# 8j-merge2.net
KiCad netlist of a schematic drawn in EAGLE
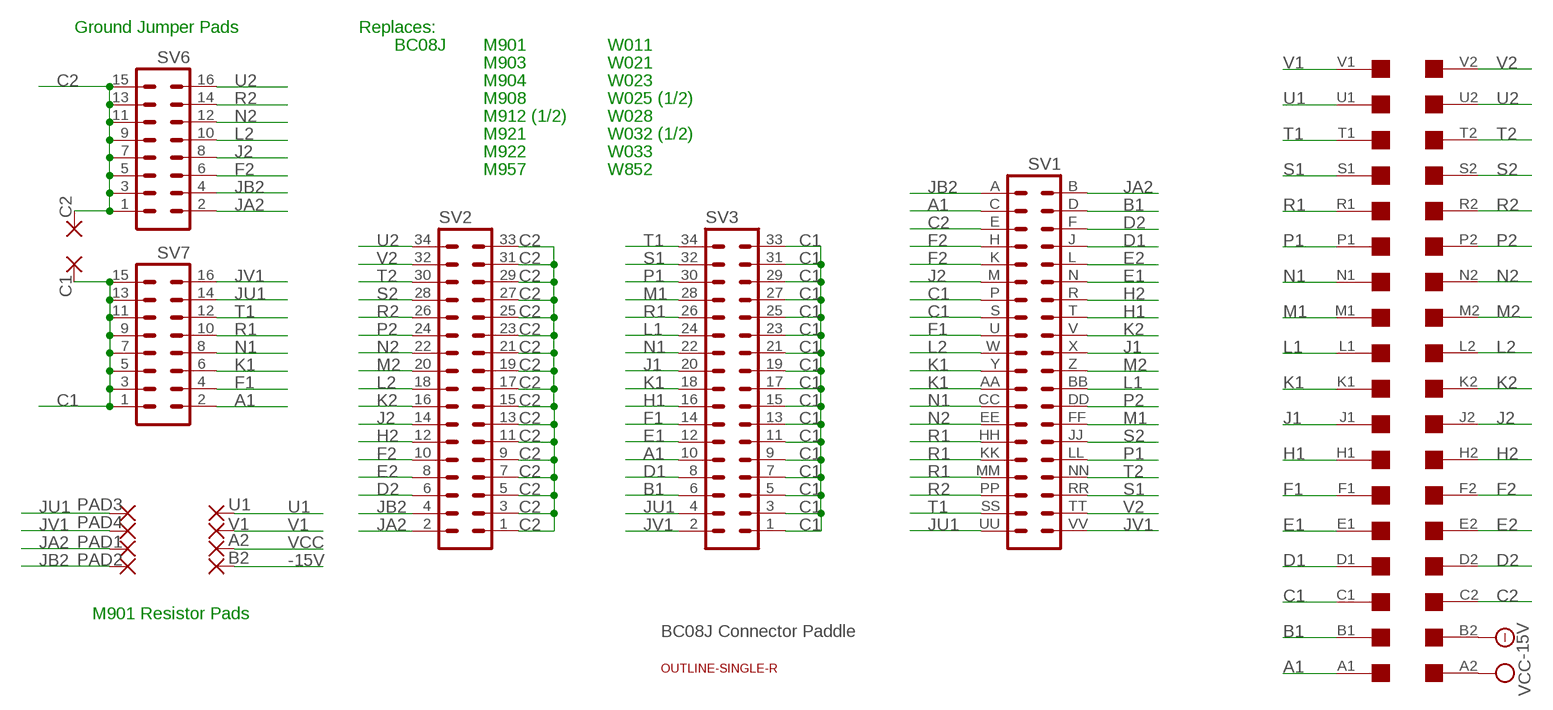
[diagram p0: schematic, sheet 1]

(export (version "E")
  (design (tool "Eeschema 10.0.6"))
  (components
    (comp (ref "A2")
      (value "1,6/0,8")
      (footprint "eagle-import:1,6_0,8")
      (libsource (lib "eagle-import") (part "1,6/0,8"))
    )
    (comp (ref "B2")
      (value "1,6/0,8")
      (footprint "eagle-import:1,6_0,8")
      (libsource (lib "eagle-import") (part "1,6/0,8"))
    )
    (comp (ref "C1")
      (value "1,6/0,8")
      (footprint "eagle-import:1,6_0,8")
      (libsource (lib "eagle-import") (part "1,6/0,8"))
    )
    (comp (ref "C2")
      (value "1,6/0,8")
      (footprint "eagle-import:1,6_0,8")
      (libsource (lib "eagle-import") (part "1,6/0,8"))
    )
    (comp (ref "PAD1")
      (value "1,6/0,8")
      (footprint "eagle-import:1,6_0,8")
      (libsource (lib "eagle-import") (part "1,6/0,8"))
    )
    (comp (ref "PAD2")
      (value "1,6/0,8")
      (footprint "eagle-import:1,6_0,8")
      (libsource (lib "eagle-import") (part "1,6/0,8"))
    )
    (comp (ref "PAD3")
      (value "1,6/0,8")
      (footprint "eagle-import:1,6_0,8")
      (libsource (lib "eagle-import") (part "1,6/0,8"))
    )
    (comp (ref "PAD4")
      (value "1,6/0,8")
      (footprint "eagle-import:1,6_0,8")
      (libsource (lib "eagle-import") (part "1,6/0,8"))
    )
    (comp (ref "SV1")
      (value "DEC40PINV")
      (footprint "eagle-import:DEC40PINV")
      (libsource (lib "eagle-import") (part "DEC40PINV"))
    )
    (comp (ref "SV2")
      (value "MA17-2")
      (footprint "eagle-import:MA17-2")
      (libsource (lib "eagle-import") (part "MA17-2"))
    )
    (comp (ref "SV3")
      (value "MA17-2")
      (footprint "eagle-import:MA17-2")
      (libsource (lib "eagle-import") (part "MA17-2"))
    )
    (comp (ref "SV6")
      (value "MA08-2")
      (footprint "eagle-import:MA08-2")
      (libsource (lib "eagle-import") (part "MA08-2"))
    )
    (comp (ref "SV7")
      (value "MA08-2")
      (footprint "eagle-import:MA08-2")
      (libsource (lib "eagle-import") (part "MA08-2"))
    )
    (comp (ref "U$1")
      (value "OUTLINE-SINGLE-R")
      (footprint "eagle-import:SINGLE-R")
      (libsource (lib "eagle-import") (part "OUTLINE-SINGLE-R"))
    )
    (comp (ref "U$2")
      (value "SINGLE")
      (footprint "eagle-import:EDGE-CON2")
      (libsource (lib "eagle-import") (part "SINGLE"))
    )
    (comp (ref "U1")
      (value "1,6/0,8")
      (footprint "eagle-import:1,6_0,8")
      (libsource (lib "eagle-import") (part "1,6/0,8"))
    )
    (comp (ref "V1")
      (value "1,6/0,8")
      (footprint "eagle-import:1,6_0,8")
      (libsource (lib "eagle-import") (part "1,6/0,8"))
    )
  )
  (nets
    (net (code "1") (name "-15V") (class "Default")
      (node (ref "B2") (pin "1") (pinfunction "P_1") (pintype "passive"))
      (node (ref "U$2") (pin "B2") (pinfunction "1_B2") (pintype "bidirectional"))
    )
    (net (code "2") (name "/A1") (class "Default")
      (node (ref "SV1") (pin "C") (pinfunction "3_C") (pintype "bidirectional"))
      (node (ref "SV3") (pin "10") (pinfunction "10_10") (pintype "passive"))
      (node (ref "SV7") (pin "2") (pinfunction "2_2") (pintype "passive"))
      (node (ref "U$2") (pin "A1") (pinfunction "1_A1") (pintype "bidirectional"))
    )
    (net (code "3") (name "/B1") (class "Default")
      (node (ref "SV1") (pin "D") (pinfunction "4_D") (pintype "bidirectional"))
      (node (ref "SV3") (pin "6") (pinfunction "6_6") (pintype "passive"))
      (node (ref "U$2") (pin "B1") (pinfunction "1_B1") (pintype "bidirectional"))
    )
    (net (code "4") (name "/C1") (class "Default")
      (node (ref "C1") (pin "1") (pinfunction "P_1") (pintype "passive"))
      (node (ref "SV1") (pin "P") (pinfunction "13_P") (pintype "bidirectional"))
      (node (ref "SV1") (pin "S") (pinfunction "15_S") (pintype "bidirectional"))
      (node (ref "SV3") (pin "1") (pinfunction "1_1") (pintype "passive"))
      (node (ref "SV3") (pin "11") (pinfunction "11_11") (pintype "passive"))
      (node (ref "SV3") (pin "13") (pinfunction "13_13") (pintype "passive"))
      (node (ref "SV3") (pin "15") (pinfunction "15_15") (pintype "passive"))
      (node (ref "SV3") (pin "17") (pinfunction "17_17") (pintype "passive"))
      (node (ref "SV3") (pin "19") (pinfunction "19_19") (pintype "passive"))
      (node (ref "SV3") (pin "21") (pinfunction "21_21") (pintype "passive"))
      (node (ref "SV3") (pin "23") (pinfunction "23_23") (pintype "passive"))
      (node (ref "SV3") (pin "25") (pinfunction "25_25") (pintype "passive"))
      (node (ref "SV3") (pin "27") (pinfunction "27_27") (pintype "passive"))
      (node (ref "SV3") (pin "29") (pinfunction "29_29") (pintype "passive"))
      (node (ref "SV3") (pin "3") (pinfunction "3_3") (pintype "passive"))
      (node (ref "SV3") (pin "31") (pinfunction "31_31") (pintype "passive"))
      (node (ref "SV3") (pin "33") (pinfunction "33_33") (pintype "passive"))
      (node (ref "SV3") (pin "5") (pinfunction "5_5") (pintype "passive"))
      (node (ref "SV3") (pin "7") (pinfunction "7_7") (pintype "passive"))
      (node (ref "SV3") (pin "9") (pinfunction "9_9") (pintype "passive"))
      (node (ref "SV7") (pin "1") (pinfunction "1_1") (pintype "passive"))
      (node (ref "SV7") (pin "11") (pinfunction "11_11") (pintype "passive"))
      (node (ref "SV7") (pin "13") (pinfunction "13_13") (pintype "passive"))
      (node (ref "SV7") (pin "15") (pinfunction "15_15") (pintype "passive"))
      (node (ref "SV7") (pin "3") (pinfunction "3_3") (pintype "passive"))
      (node (ref "SV7") (pin "5") (pinfunction "5_5") (pintype "passive"))
      (node (ref "SV7") (pin "7") (pinfunction "7_7") (pintype "passive"))
      (node (ref "SV7") (pin "9") (pinfunction "9_9") (pintype "passive"))
      (node (ref "U$2") (pin "C1") (pinfunction "1_C1") (pintype "bidirectional"))
    )
    (net (code "5") (name "/C2") (class "Default")
      (node (ref "C2") (pin "1") (pinfunction "P_1") (pintype "passive"))
      (node (ref "SV1") (pin "E") (pinfunction "5_E") (pintype "bidirectional"))
      (node (ref "SV2") (pin "1") (pinfunction "1_1") (pintype "passive"))
      (node (ref "SV2") (pin "11") (pinfunction "11_11") (pintype "passive"))
      (node (ref "SV2") (pin "13") (pinfunction "13_13") (pintype "passive"))
      (node (ref "SV2") (pin "15") (pinfunction "15_15") (pintype "passive"))
      (node (ref "SV2") (pin "17") (pinfunction "17_17") (pintype "passive"))
      (node (ref "SV2") (pin "19") (pinfunction "19_19") (pintype "passive"))
      (node (ref "SV2") (pin "21") (pinfunction "21_21") (pintype "passive"))
      (node (ref "SV2") (pin "23") (pinfunction "23_23") (pintype "passive"))
      (node (ref "SV2") (pin "25") (pinfunction "25_25") (pintype "passive"))
      (node (ref "SV2") (pin "27") (pinfunction "27_27") (pintype "passive"))
      (node (ref "SV2") (pin "29") (pinfunction "29_29") (pintype "passive"))
      (node (ref "SV2") (pin "3") (pinfunction "3_3") (pintype "passive"))
      (node (ref "SV2") (pin "31") (pinfunction "31_31") (pintype "passive"))
      (node (ref "SV2") (pin "33") (pinfunction "33_33") (pintype "passive"))
      (node (ref "SV2") (pin "5") (pinfunction "5_5") (pintype "passive"))
      (node (ref "SV2") (pin "7") (pinfunction "7_7") (pintype "passive"))
      (node (ref "SV2") (pin "9") (pinfunction "9_9") (pintype "passive"))
      (node (ref "SV6") (pin "1") (pinfunction "1_1") (pintype "passive"))
      (node (ref "SV6") (pin "11") (pinfunction "11_11") (pintype "passive"))
      (node (ref "SV6") (pin "13") (pinfunction "13_13") (pintype "passive"))
      (node (ref "SV6") (pin "15") (pinfunction "15_15") (pintype "passive"))
      (node (ref "SV6") (pin "3") (pinfunction "3_3") (pintype "passive"))
      (node (ref "SV6") (pin "5") (pinfunction "5_5") (pintype "passive"))
      (node (ref "SV6") (pin "7") (pinfunction "7_7") (pintype "passive"))
      (node (ref "SV6") (pin "9") (pinfunction "9_9") (pintype "passive"))
      (node (ref "U$2") (pin "C2") (pinfunction "1_C2") (pintype "bidirectional"))
    )
    (net (code "6") (name "/D1") (class "Default")
      (node (ref "SV1") (pin "J") (pinfunction "8_J") (pintype "bidirectional"))
      (node (ref "SV3") (pin "8") (pinfunction "8_8") (pintype "passive"))
      (node (ref "U$2") (pin "D1") (pinfunction "1_D1") (pintype "bidirectional"))
    )
    (net (code "7") (name "/D2") (class "Default")
      (node (ref "SV1") (pin "F") (pinfunction "6_F") (pintype "bidirectional"))
      (node (ref "SV2") (pin "6") (pinfunction "6_6") (pintype "passive"))
      (node (ref "U$2") (pin "D2") (pinfunction "1_D2") (pintype "bidirectional"))
    )
    (net (code "8") (name "/E1") (class "Default")
      (node (ref "SV1") (pin "N") (pinfunction "12_N") (pintype "bidirectional"))
      (node (ref "SV3") (pin "12") (pinfunction "12_12") (pintype "passive"))
      (node (ref "U$2") (pin "E1") (pinfunction "1_E1") (pintype "bidirectional"))
    )
    (net (code "9") (name "/E2") (class "Default")
      (node (ref "SV1") (pin "L") (pinfunction "10_L") (pintype "bidirectional"))
      (node (ref "SV2") (pin "8") (pinfunction "8_8") (pintype "passive"))
      (node (ref "U$2") (pin "E2") (pinfunction "1_E2") (pintype "bidirectional"))
    )
    (net (code "10") (name "/F1") (class "Default")
      (node (ref "SV1") (pin "U") (pinfunction "17_U") (pintype "bidirectional"))
      (node (ref "SV3") (pin "14") (pinfunction "14_14") (pintype "passive"))
      (node (ref "SV7") (pin "4") (pinfunction "4_4") (pintype "passive"))
      (node (ref "U$2") (pin "F1") (pinfunction "1_F1") (pintype "bidirectional"))
    )
    (net (code "11") (name "/F2") (class "Default")
      (node (ref "SV1") (pin "H") (pinfunction "7_H") (pintype "bidirectional"))
      (node (ref "SV1") (pin "K") (pinfunction "9_K") (pintype "bidirectional"))
      (node (ref "SV2") (pin "10") (pinfunction "10_10") (pintype "passive"))
      (node (ref "SV6") (pin "6") (pinfunction "6_6") (pintype "passive"))
      (node (ref "U$2") (pin "F2") (pinfunction "1_F2") (pintype "bidirectional"))
    )
    (net (code "12") (name "/H1") (class "Default")
      (node (ref "SV1") (pin "T") (pinfunction "16_T") (pintype "bidirectional"))
      (node (ref "SV3") (pin "16") (pinfunction "16_16") (pintype "passive"))
      (node (ref "U$2") (pin "H1") (pinfunction "1_H1") (pintype "bidirectional"))
    )
    (net (code "13") (name "/H2") (class "Default")
      (node (ref "SV1") (pin "R") (pinfunction "14_R") (pintype "bidirectional"))
      (node (ref "SV2") (pin "12") (pinfunction "12_12") (pintype "passive"))
      (node (ref "U$2") (pin "H2") (pinfunction "1_H2") (pintype "bidirectional"))
    )
    (net (code "14") (name "/J1") (class "Default")
      (node (ref "SV1") (pin "X") (pinfunction "20_X") (pintype "bidirectional"))
      (node (ref "SV3") (pin "20") (pinfunction "20_20") (pintype "passive"))
      (node (ref "U$2") (pin "J1") (pinfunction "1_J1") (pintype "bidirectional"))
    )
    (net (code "15") (name "/J2") (class "Default")
      (node (ref "SV1") (pin "M") (pinfunction "11_M") (pintype "bidirectional"))
      (node (ref "SV2") (pin "14") (pinfunction "14_14") (pintype "passive"))
      (node (ref "SV6") (pin "8") (pinfunction "8_8") (pintype "passive"))
      (node (ref "U$2") (pin "J2") (pinfunction "1_J2") (pintype "bidirectional"))
    )
    (net (code "16") (name "/JA2") (class "Default")
      (node (ref "PAD1") (pin "1") (pinfunction "P_1") (pintype "passive"))
      (node (ref "SV1") (pin "B") (pinfunction "2_B") (pintype "bidirectional"))
      (node (ref "SV2") (pin "2") (pinfunction "2_2") (pintype "passive"))
      (node (ref "SV6") (pin "2") (pinfunction "2_2") (pintype "passive"))
    )
    (net (code "17") (name "/JB2") (class "Default")
      (node (ref "PAD2") (pin "1") (pinfunction "P_1") (pintype "passive"))
      (node (ref "SV1") (pin "A") (pinfunction "1_A") (pintype "bidirectional"))
      (node (ref "SV2") (pin "4") (pinfunction "4_4") (pintype "passive"))
      (node (ref "SV6") (pin "4") (pinfunction "4_4") (pintype "passive"))
    )
    (net (code "18") (name "/JU1") (class "Default")
      (node (ref "PAD3") (pin "1") (pinfunction "P_1") (pintype "passive"))
      (node (ref "SV1") (pin "UU") (pinfunction "39_UU") (pintype "bidirectional"))
      (node (ref "SV3") (pin "4") (pinfunction "4_4") (pintype "passive"))
      (node (ref "SV7") (pin "14") (pinfunction "14_14") (pintype "passive"))
    )
    (net (code "19") (name "/JV1") (class "Default")
      (node (ref "PAD4") (pin "1") (pinfunction "P_1") (pintype "passive"))
      (node (ref "SV1") (pin "VV") (pinfunction "40_VV") (pintype "bidirectional"))
      (node (ref "SV3") (pin "2") (pinfunction "2_2") (pintype "passive"))
      (node (ref "SV7") (pin "16") (pinfunction "16_16") (pintype "passive"))
    )
    (net (code "20") (name "/K1") (class "Default")
      (node (ref "SV1") (pin "AA") (pinfunction "23_AA") (pintype "bidirectional"))
      (node (ref "SV1") (pin "Y") (pinfunction "21_Y") (pintype "bidirectional"))
      (node (ref "SV3") (pin "18") (pinfunction "18_18") (pintype "passive"))
      (node (ref "SV7") (pin "6") (pinfunction "6_6") (pintype "passive"))
      (node (ref "U$2") (pin "K1") (pinfunction "1_K1") (pintype "bidirectional"))
    )
    (net (code "21") (name "/K2") (class "Default")
      (node (ref "SV1") (pin "V") (pinfunction "18_V") (pintype "bidirectional"))
      (node (ref "SV2") (pin "16") (pinfunction "16_16") (pintype "passive"))
      (node (ref "U$2") (pin "K2") (pinfunction "1_K2") (pintype "bidirectional"))
    )
    (net (code "22") (name "/L1") (class "Default")
      (node (ref "SV1") (pin "BB") (pinfunction "24_BB") (pintype "bidirectional"))
      (node (ref "SV3") (pin "24") (pinfunction "24_24") (pintype "passive"))
      (node (ref "U$2") (pin "L1") (pinfunction "1_L1") (pintype "bidirectional"))
    )
    (net (code "23") (name "/L2") (class "Default")
      (node (ref "SV1") (pin "W") (pinfunction "19_W") (pintype "bidirectional"))
      (node (ref "SV2") (pin "18") (pinfunction "18_18") (pintype "passive"))
      (node (ref "SV6") (pin "10") (pinfunction "10_10") (pintype "passive"))
      (node (ref "U$2") (pin "L2") (pinfunction "1_L2") (pintype "bidirectional"))
    )
    (net (code "24") (name "/M1") (class "Default")
      (node (ref "SV1") (pin "FF") (pinfunction "28_FF") (pintype "bidirectional"))
      (node (ref "SV3") (pin "28") (pinfunction "28_28") (pintype "passive"))
      (node (ref "U$2") (pin "M1") (pinfunction "1_M1") (pintype "bidirectional"))
    )
    (net (code "25") (name "/M2") (class "Default")
      (node (ref "SV1") (pin "Z") (pinfunction "22_Z") (pintype "bidirectional"))
      (node (ref "SV2") (pin "20") (pinfunction "20_20") (pintype "passive"))
      (node (ref "U$2") (pin "M2") (pinfunction "1_M2") (pintype "bidirectional"))
    )
    (net (code "26") (name "/N1") (class "Default")
      (node (ref "SV1") (pin "CC") (pinfunction "25_CC") (pintype "bidirectional"))
      (node (ref "SV3") (pin "22") (pinfunction "22_22") (pintype "passive"))
      (node (ref "SV7") (pin "8") (pinfunction "8_8") (pintype "passive"))
      (node (ref "U$2") (pin "N1") (pinfunction "1_N1") (pintype "bidirectional"))
    )
    (net (code "27") (name "/N2") (class "Default")
      (node (ref "SV1") (pin "EE") (pinfunction "27_EE") (pintype "bidirectional"))
      (node (ref "SV2") (pin "22") (pinfunction "22_22") (pintype "passive"))
      (node (ref "SV6") (pin "12") (pinfunction "12_12") (pintype "passive"))
      (node (ref "U$2") (pin "N2") (pinfunction "1_N2") (pintype "bidirectional"))
    )
    (net (code "28") (name "/P1") (class "Default")
      (node (ref "SV1") (pin "LL") (pinfunction "32_LL") (pintype "bidirectional"))
      (node (ref "SV3") (pin "30") (pinfunction "30_30") (pintype "passive"))
      (node (ref "U$2") (pin "P1") (pinfunction "1_P1") (pintype "bidirectional"))
    )
    (net (code "29") (name "/P2") (class "Default")
      (node (ref "SV1") (pin "DD") (pinfunction "26_DD") (pintype "bidirectional"))
      (node (ref "SV2") (pin "24") (pinfunction "24_24") (pintype "passive"))
      (node (ref "U$2") (pin "P2") (pinfunction "1_P2") (pintype "bidirectional"))
    )
    (net (code "30") (name "/R1") (class "Default")
      (node (ref "SV1") (pin "HH") (pinfunction "29_HH") (pintype "bidirectional"))
      (node (ref "SV1") (pin "KK") (pinfunction "31_KK") (pintype "bidirectional"))
      (node (ref "SV1") (pin "MM") (pinfunction "33_MM") (pintype "bidirectional"))
      (node (ref "SV3") (pin "26") (pinfunction "26_26") (pintype "passive"))
      (node (ref "SV7") (pin "10") (pinfunction "10_10") (pintype "passive"))
      (node (ref "U$2") (pin "R1") (pinfunction "1_R1") (pintype "bidirectional"))
    )
    (net (code "31") (name "/R2") (class "Default")
      (node (ref "SV1") (pin "PP") (pinfunction "35_PP") (pintype "bidirectional"))
      (node (ref "SV2") (pin "26") (pinfunction "26_26") (pintype "passive"))
      (node (ref "SV6") (pin "14") (pinfunction "14_14") (pintype "passive"))
      (node (ref "U$2") (pin "R2") (pinfunction "1_R2") (pintype "bidirectional"))
    )
    (net (code "32") (name "/S1") (class "Default")
      (node (ref "SV1") (pin "RR") (pinfunction "36_RR") (pintype "bidirectional"))
      (node (ref "SV3") (pin "32") (pinfunction "32_32") (pintype "passive"))
      (node (ref "U$2") (pin "S1") (pinfunction "1_S1") (pintype "bidirectional"))
    )
    (net (code "33") (name "/S2") (class "Default")
      (node (ref "SV1") (pin "JJ") (pinfunction "30_JJ") (pintype "bidirectional"))
      (node (ref "SV2") (pin "28") (pinfunction "28_28") (pintype "passive"))
      (node (ref "U$2") (pin "S2") (pinfunction "1_S2") (pintype "bidirectional"))
    )
    (net (code "34") (name "/T1") (class "Default")
      (node (ref "SV1") (pin "SS") (pinfunction "37_SS") (pintype "bidirectional"))
      (node (ref "SV3") (pin "34") (pinfunction "34_34") (pintype "passive"))
      (node (ref "SV7") (pin "12") (pinfunction "12_12") (pintype "passive"))
      (node (ref "U$2") (pin "T1") (pinfunction "1_T1") (pintype "bidirectional"))
    )
    (net (code "35") (name "/T2") (class "Default")
      (node (ref "SV1") (pin "NN") (pinfunction "34_NN") (pintype "bidirectional"))
      (node (ref "SV2") (pin "30") (pinfunction "30_30") (pintype "passive"))
      (node (ref "U$2") (pin "T2") (pinfunction "1_T2") (pintype "bidirectional"))
    )
    (net (code "36") (name "/U1") (class "Default")
      (node (ref "U$2") (pin "U1") (pinfunction "1_U1") (pintype "bidirectional"))
      (node (ref "U1") (pin "1") (pinfunction "P_1") (pintype "passive"))
    )
    (net (code "37") (name "/U2") (class "Default")
      (node (ref "SV2") (pin "34") (pinfunction "34_34") (pintype "passive"))
      (node (ref "SV6") (pin "16") (pinfunction "16_16") (pintype "passive"))
      (node (ref "U$2") (pin "U2") (pinfunction "1_U2") (pintype "bidirectional"))
    )
    (net (code "38") (name "/V1") (class "Default")
      (node (ref "U$2") (pin "V1") (pinfunction "1_V1") (pintype "bidirectional"))
      (node (ref "V1") (pin "1") (pinfunction "P_1") (pintype "passive"))
    )
    (net (code "39") (name "/V2") (class "Default")
      (node (ref "SV1") (pin "TT") (pinfunction "38_TT") (pintype "bidirectional"))
      (node (ref "SV2") (pin "32") (pinfunction "32_32") (pintype "passive"))
      (node (ref "U$2") (pin "V2") (pinfunction "1_V2") (pintype "bidirectional"))
    )
    (net (code "40") (name "VCC") (class "Default")
      (node (ref "A2") (pin "1") (pinfunction "P_1") (pintype "passive"))
      (node (ref "U$2") (pin "A2") (pinfunction "1_A2") (pintype "bidirectional"))
    )
  )
)
